# tick-tiny-mk-2_0.net
KiCad netlist of a schematic drawn in EAGLE
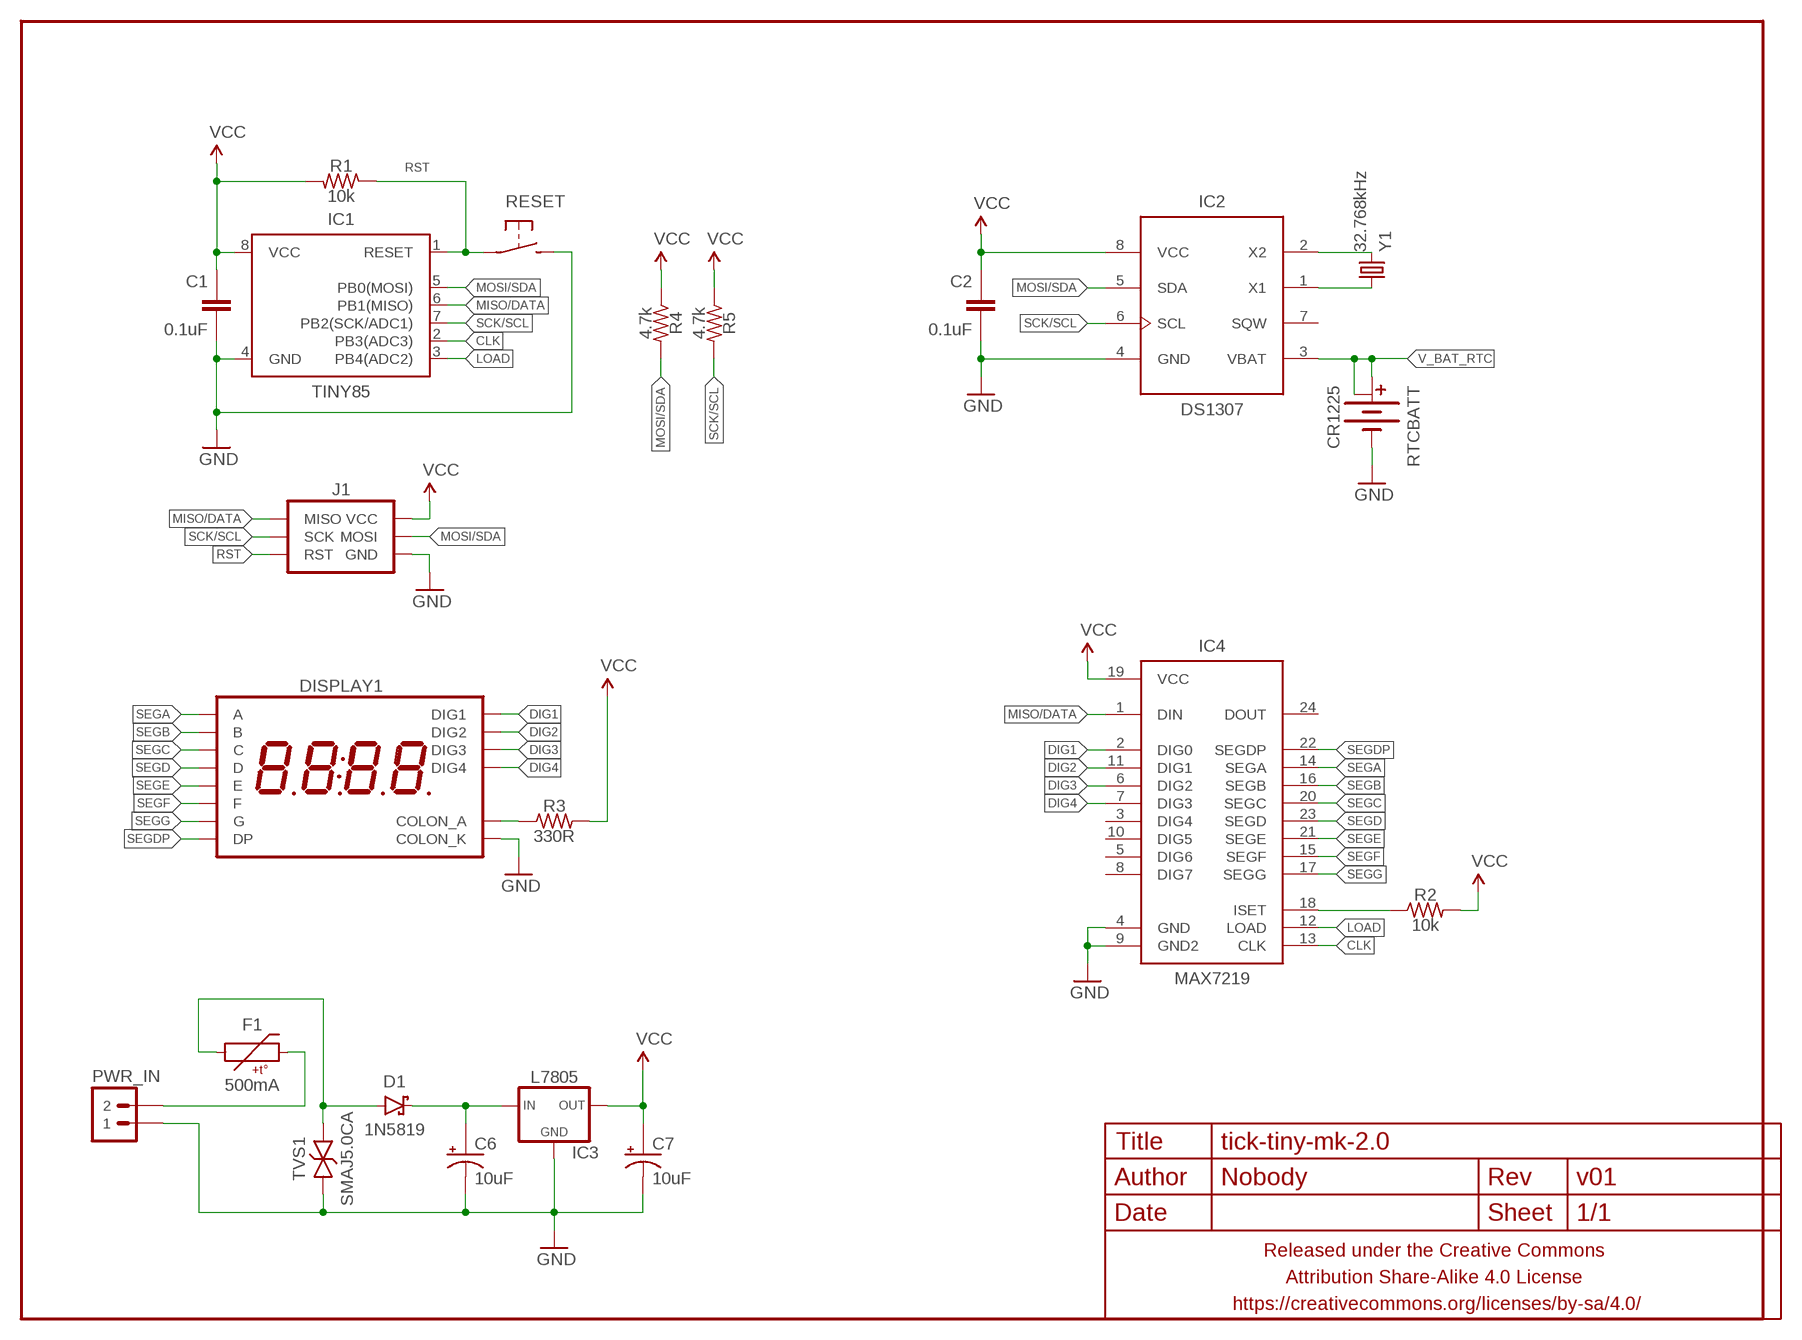
[diagram p0: schematic, sheet 1]

(export (version "E")
  (design (tool "Eeschema 10.0.6"))
  (components
    (comp (ref "C1")
      (value "0.1uF")
      (footprint "eagle-import:C025-024X044")
      (libsource (lib "eagle-import") (part "CAPACITOR-CERAMIC025-024X044"))
    )
    (comp (ref "C2")
      (value "0.1uF")
      (footprint "eagle-import:C025-024X044")
      (libsource (lib "eagle-import") (part "CAPACITOR-CERAMIC025-024X044"))
    )
    (comp (ref "C6")
      (value "10uF")
      (footprint "eagle-import:E2-5")
      (libsource (lib "eagle-import") (part "CAPACITOR-POLARIZEDE2-5"))
    )
    (comp (ref "C7")
      (value "10uF")
      (footprint "eagle-import:E2-5")
      (libsource (lib "eagle-import") (part "CAPACITOR-POLARIZEDE2-5"))
    )
    (comp (ref "D1")
      (value "1N5819")
      (footprint "eagle-import:DIODE-10.16MM")
      (libsource (lib "eagle-import") (part "DIODE-SCHOTTKYPTH-10.16MM"))
    )
    (comp (ref "DISPLAY1")
      (value "7SEG_4DIGIT_COLON14.2MM-CC-NS")
      (footprint "eagle-import:7SEG_4DIG_NS")
      (libsource (lib "eagle-import") (part "7SEG_4DIGIT_COLON14.2MM-CC-NS"))
    )
    (comp (ref "F1")
      (value "500mA")
      (footprint "eagle-import:PTC-PTH-5.08MM")
      (libsource (lib "eagle-import") (part "PTCPTH-5.08MM"))
    )
    (comp (ref "FRAME1")
      (value "FRAME-LETTERNO_PACKAGE")
      (footprint "eagle-import:DUMMY")
      (fields (field (name "DESIGNER") "Nobody"))
      (libsource (lib "eagle-import") (part "FRAME-LETTERNO_PACKAGE"))
    )
    (comp (ref "IC1")
      (value "TINY85")
      (footprint "eagle-import:DIP08")
      (libsource (lib "eagle-import") (part "ATTINY45TINY85-20-DIP"))
    )
    (comp (ref "IC2")
      (value "DS1307")
      (footprint "eagle-import:DIL08")
      (libsource (lib "eagle-import") (part "DS1307"))
    )
    (comp (ref "IC3")
      (value "L7805")
      (footprint "eagle-import:TO-92-AMMO")
      (libsource (lib "eagle-import") (part "V_REG_78XXTO-92-INLINE"))
    )
    (comp (ref "IC4")
      (value "MAX7219")
      (footprint "eagle-import:SO24W")
      (libsource (lib "eagle-import") (part "MAX7219SOIC-W"))
    )
    (comp (ref "J1")
      (value "AVR_SPI_PRG_6PTH")
      (footprint "eagle-import:2X3")
      (libsource (lib "eagle-import") (part "AVR_SPI_PRG_6PTH"))
    )
    (comp (ref "PWR_IN")
      (value "M02JST-PTH-RA-R+")
      (footprint "eagle-import:JST-2-PH-RA-PTH-R+")
      (libsource (lib "eagle-import") (part "M02JST-PTH-RA-R+"))
    )
    (comp (ref "R1")
      (value "10k")
      (footprint "eagle-import:RESISTOR-AXIAL-PTH-7.62MM")
      (libsource (lib "eagle-import") (part "RESISTORPTH-AXIAL-7.62MM"))
    )
    (comp (ref "R2")
      (value "10k")
      (footprint "eagle-import:RESISTOR-AXIAL-PTH-5.08MM")
      (libsource (lib "eagle-import") (part "RESISTORPTH-AXIAL-5.08MM"))
    )
    (comp (ref "R3")
      (value "330R")
      (footprint "eagle-import:RESISTOR-AXIAL-PTH-5.08MM")
      (libsource (lib "eagle-import") (part "RESISTORPTH-AXIAL-5.08MM"))
    )
    (comp (ref "R4")
      (value "4.7k")
      (footprint "eagle-import:RESISTOR-AXIAL-PTH-7.62MM")
      (libsource (lib "eagle-import") (part "RESISTORPTH-AXIAL-7.62MM"))
    )
    (comp (ref "R5")
      (value "4.7k")
      (footprint "eagle-import:RESISTOR-AXIAL-PTH-7.62MM")
      (libsource (lib "eagle-import") (part "RESISTORPTH-AXIAL-7.62MM"))
    )
    (comp (ref "RESET")
      (value "SPST-NO-TACT3MM-PTH-SMALL-PADS")
      (footprint "eagle-import:DTS-3-SMALL-PADS")
      (libsource (lib "eagle-import") (part "SPST-NO-TACT3MM-PTH-SMALL-PADS"))
    )
    (comp (ref "RTCBATT")
      (value "CR1225")
      (footprint "eagle-import:BATTCON_12MM_SMD")
      (libsource (lib "eagle-import") (part "BATTERY-COINCR1225_SMD_SMALLER"))
    )
    (comp (ref "TVS1")
      (value "SMAJ5.0CA")
      (footprint "eagle-import:DO-41-TVS-BI-10.16MM")
      (libsource (lib "eagle-import") (part "TVSDO-41-10.16MM"))
    )
    (comp (ref "Y1")
      (value "32.768kHz")
      (footprint "eagle-import:TC26H")
      (libsource (lib "eagle-import") (part "CRYSTALTC26H"))
    )
  )
  (nets
    (net (code "1") (name "CLK") (class "Default")
      (node (ref "IC1") (pin "2") (pinfunction "PB3(ADC3)_2") (pintype "bidirectional"))
      (node (ref "IC4") (pin "13") (pinfunction "CLK_13") (pintype "bidirectional"))
    )
    (net (code "2") (name "DIG1") (class "Default")
      (node (ref "DISPLAY1") (pin "P$14") (pinfunction "DIG1_P$14") (pintype "passive"))
      (node (ref "IC4") (pin "2") (pinfunction "DIG0_2") (pintype "bidirectional"))
    )
    (net (code "3") (name "DIG2") (class "Default")
      (node (ref "DISPLAY1") (pin "P$11") (pinfunction "DIG2_P$11") (pintype "passive"))
      (node (ref "IC4") (pin "11") (pinfunction "DIG1_11") (pintype "bidirectional"))
    )
    (net (code "4") (name "DIG3") (class "Default")
      (node (ref "DISPLAY1") (pin "P$10") (pinfunction "DIG3_P$10") (pintype "passive"))
      (node (ref "IC4") (pin "6") (pinfunction "DIG2_6") (pintype "bidirectional"))
    )
    (net (code "5") (name "DIG4") (class "Default")
      (node (ref "DISPLAY1") (pin "P$6") (pinfunction "DIG4_P$6") (pintype "passive"))
      (node (ref "IC4") (pin "7") (pinfunction "DIG3_7") (pintype "bidirectional"))
    )
    (net (code "6") (name "GND") (class "Default")
      (node (ref "C1") (pin "2") (pinfunction "2_2") (pintype "passive"))
      (node (ref "C2") (pin "2") (pinfunction "2_2") (pintype "passive"))
      (node (ref "C6") (pin "-") (pinfunction "-_-") (pintype "passive"))
      (node (ref "C7") (pin "-") (pinfunction "-_-") (pintype "passive"))
      (node (ref "DISPLAY1") (pin "P$7") (pinfunction "COLON_K_P$7") (pintype "passive"))
      (node (ref "IC1") (pin "4") (pinfunction "GND_4") (pintype "bidirectional"))
      (node (ref "IC2") (pin "4") (pinfunction "GND_4") (pintype "power_in"))
      (node (ref "IC3") (pin "2") (pinfunction "GND_2") (pintype "bidirectional"))
      (node (ref "IC4") (pin "4") (pinfunction "GND_4") (pintype "bidirectional"))
      (node (ref "IC4") (pin "9") (pinfunction "GND2_9") (pintype "bidirectional"))
      (node (ref "J1") (pin "6") (pinfunction "GND_6") (pintype "passive"))
      (node (ref "PWR_IN") (pin "1") (pinfunction "1_1") (pintype "passive"))
      (node (ref "RESET") (pin "2") (pinfunction "2_2") (pintype "passive"))
      (node (ref "RTCBATT") (pin "-") (pinfunction "-_-") (pintype "bidirectional"))
      (node (ref "TVS1") (pin "P$1") (pinfunction "1_P$1") (pintype "passive"))
    )
    (net (code "7") (name "LOAD") (class "Default")
      (node (ref "IC1") (pin "3") (pinfunction "PB4(ADC2)_3") (pintype "bidirectional"))
      (node (ref "IC4") (pin "12") (pinfunction "LOAD_12") (pintype "bidirectional"))
    )
    (net (code "8") (name "MISO{slash}DATA") (class "Default")
      (node (ref "IC1") (pin "6") (pinfunction "PB1(MISO)_6") (pintype "bidirectional"))
      (node (ref "IC4") (pin "1") (pinfunction "DIN_1") (pintype "bidirectional"))
      (node (ref "J1") (pin "1") (pinfunction "MISO_1") (pintype "passive"))
    )
    (net (code "9") (name "MOSI{slash}SDA") (class "Default")
      (node (ref "IC1") (pin "5") (pinfunction "PB0(MOSI)_5") (pintype "bidirectional"))
      (node (ref "IC2") (pin "5") (pinfunction "SDA_5") (pintype "bidirectional"))
      (node (ref "J1") (pin "4") (pinfunction "MOSI_4") (pintype "passive"))
      (node (ref "R4") (pin "P$2") (pinfunction "2_P$2") (pintype "passive"))
    )
    (net (code "10") (name "Net-(DISPLAY1-COLON_A)") (class "Default")
      (node (ref "DISPLAY1") (pin "P$8") (pinfunction "COLON_A_P$8") (pintype "passive"))
      (node (ref "R3") (pin "P$1") (pinfunction "1_P$1") (pintype "passive"))
    )
    (net (code "11") (name "Net-(F1-1)") (class "Default")
      (node (ref "D1") (pin "A") (pinfunction "A_A") (pintype "passive"))
      (node (ref "F1") (pin "P$1") (pinfunction "1_P$1") (pintype "passive"))
      (node (ref "TVS1") (pin "P$2") (pinfunction "2_P$2") (pintype "passive"))
    )
    (net (code "12") (name "Net-(F1-2)") (class "Default")
      (node (ref "F1") (pin "P$2") (pinfunction "2_P$2") (pintype "passive"))
      (node (ref "PWR_IN") (pin "2") (pinfunction "2_2") (pintype "passive"))
    )
    (net (code "13") (name "Net-(IC2-X1)") (class "Default")
      (node (ref "IC2") (pin "1") (pinfunction "X1_1") (pintype "passive"))
      (node (ref "Y1") (pin "1") (pinfunction "1_1") (pintype "passive"))
    )
    (net (code "14") (name "Net-(IC2-X2)") (class "Default")
      (node (ref "IC2") (pin "2") (pinfunction "X2_2") (pintype "passive"))
      (node (ref "Y1") (pin "2") (pinfunction "2_2") (pintype "passive"))
    )
    (net (code "15") (name "Net-(IC3-IN)") (class "Default")
      (node (ref "C6") (pin "+") (pinfunction "+_+") (pintype "passive"))
      (node (ref "D1") (pin "C") (pinfunction "C_C") (pintype "passive"))
      (node (ref "IC3") (pin "1") (pinfunction "IN_1") (pintype "bidirectional"))
    )
    (net (code "16") (name "Net-(IC4-ISET)") (class "Default")
      (node (ref "IC4") (pin "18") (pinfunction "ISET_18") (pintype "bidirectional"))
      (node (ref "R2") (pin "P$1") (pinfunction "1_P$1") (pintype "passive"))
    )
    (net (code "17") (name "RST") (class "Default")
      (node (ref "IC1") (pin "1") (pinfunction "RESET_1") (pintype "bidirectional"))
      (node (ref "J1") (pin "5") (pinfunction "RST_5") (pintype "passive"))
      (node (ref "R1") (pin "P$1") (pinfunction "1_P$1") (pintype "passive"))
      (node (ref "RESET") (pin "1") (pinfunction "1_1") (pintype "passive"))
    )
    (net (code "18") (name "SCK{slash}SCL") (class "Default")
      (node (ref "IC1") (pin "7") (pinfunction "PB2(SCK/ADC1)_7") (pintype "bidirectional"))
      (node (ref "IC2") (pin "6") (pinfunction "SCL_6") (pintype "bidirectional"))
      (node (ref "J1") (pin "3") (pinfunction "SCK_3") (pintype "passive"))
      (node (ref "R5") (pin "P$2") (pinfunction "2_P$2") (pintype "passive"))
    )
    (net (code "19") (name "SEGA") (class "Default")
      (node (ref "DISPLAY1") (pin "P$13") (pinfunction "A_P$13") (pintype "passive"))
      (node (ref "IC4") (pin "14") (pinfunction "SEGA_14") (pintype "bidirectional"))
    )
    (net (code "20") (name "SEGB") (class "Default")
      (node (ref "DISPLAY1") (pin "P$9") (pinfunction "B_P$9") (pintype "passive"))
      (node (ref "IC4") (pin "16") (pinfunction "SEGB_16") (pintype "bidirectional"))
    )
    (net (code "21") (name "SEGC") (class "Default")
      (node (ref "DISPLAY1") (pin "P$4") (pinfunction "C_P$4") (pintype "passive"))
      (node (ref "IC4") (pin "20") (pinfunction "SEGC_20") (pintype "bidirectional"))
    )
    (net (code "22") (name "SEGD") (class "Default")
      (node (ref "DISPLAY1") (pin "P$2") (pinfunction "D_P$2") (pintype "passive"))
      (node (ref "IC4") (pin "23") (pinfunction "SEGD_23") (pintype "bidirectional"))
    )
    (net (code "23") (name "SEGDP") (class "Default")
      (node (ref "DISPLAY1") (pin "P$3") (pinfunction "DP_P$3") (pintype "passive"))
      (node (ref "IC4") (pin "22") (pinfunction "SEGDP_22") (pintype "bidirectional"))
    )
    (net (code "24") (name "SEGE") (class "Default")
      (node (ref "DISPLAY1") (pin "P$1") (pinfunction "E_P$1") (pintype "passive"))
      (node (ref "IC4") (pin "21") (pinfunction "SEGE_21") (pintype "bidirectional"))
    )
    (net (code "25") (name "SEGF") (class "Default")
      (node (ref "DISPLAY1") (pin "P$12") (pinfunction "F_P$12") (pintype "passive"))
      (node (ref "IC4") (pin "15") (pinfunction "SEGF_15") (pintype "bidirectional"))
    )
    (net (code "26") (name "SEGG") (class "Default")
      (node (ref "DISPLAY1") (pin "P$5") (pinfunction "G_P$5") (pintype "passive"))
      (node (ref "IC4") (pin "17") (pinfunction "SEGG_17") (pintype "bidirectional"))
    )
    (net (code "27") (name "VCC") (class "Default")
      (node (ref "C1") (pin "1") (pinfunction "1_1") (pintype "passive"))
      (node (ref "C2") (pin "1") (pinfunction "1_1") (pintype "passive"))
      (node (ref "C7") (pin "+") (pinfunction "+_+") (pintype "passive"))
      (node (ref "IC1") (pin "8") (pinfunction "VCC_8") (pintype "bidirectional"))
      (node (ref "IC2") (pin "8") (pinfunction "VCC_8") (pintype "power_in"))
      (node (ref "IC3") (pin "3") (pinfunction "OUT_3") (pintype "bidirectional"))
      (node (ref "IC4") (pin "19") (pinfunction "VCC_19") (pintype "bidirectional"))
      (node (ref "J1") (pin "2") (pinfunction "VCC_2") (pintype "passive"))
      (node (ref "R1") (pin "P$2") (pinfunction "2_P$2") (pintype "passive"))
      (node (ref "R2") (pin "P$2") (pinfunction "2_P$2") (pintype "passive"))
      (node (ref "R3") (pin "P$2") (pinfunction "2_P$2") (pintype "passive"))
      (node (ref "R4") (pin "P$1") (pinfunction "1_P$1") (pintype "passive"))
      (node (ref "R5") (pin "P$1") (pinfunction "1_P$1") (pintype "passive"))
    )
    (net (code "28") (name "V_BAT_RTC") (class "Default")
      (node (ref "IC2") (pin "3") (pinfunction "VBAT_3") (pintype "power_in"))
      (node (ref "RTCBATT") (pin "+@1") (pinfunction "+_+@1") (pintype "bidirectional"))
      (node (ref "RTCBATT") (pin "+@2") (pinfunction "+1_+@2") (pintype "bidirectional"))
    )
    (net (code "29") (name "unconnected-(IC2-SQW-Pad7)") (class "Default")
      (node (ref "IC2") (pin "7") (pinfunction "SQW_7") (pintype "bidirectional"))
    )
    (net (code "30") (name "unconnected-(IC4-DIG4-Pad3)") (class "Default")
      (node (ref "IC4") (pin "3") (pinfunction "DIG4_3") (pintype "bidirectional"))
    )
    (net (code "31") (name "unconnected-(IC4-DIG5-Pad10)") (class "Default")
      (node (ref "IC4") (pin "10") (pinfunction "DIG5_10") (pintype "bidirectional"))
    )
    (net (code "32") (name "unconnected-(IC4-DIG6-Pad5)") (class "Default")
      (node (ref "IC4") (pin "5") (pinfunction "DIG6_5") (pintype "bidirectional"))
    )
    (net (code "33") (name "unconnected-(IC4-DIG7-Pad8)") (class "Default")
      (node (ref "IC4") (pin "8") (pinfunction "DIG7_8") (pintype "bidirectional"))
    )
    (net (code "34") (name "unconnected-(IC4-DOUT-Pad24)") (class "Default")
      (node (ref "IC4") (pin "24") (pinfunction "DOUT_24") (pintype "bidirectional"))
    )
  )
)
